# Led_block.net
KiCad netlist of a schematic drawn in Altium Designer
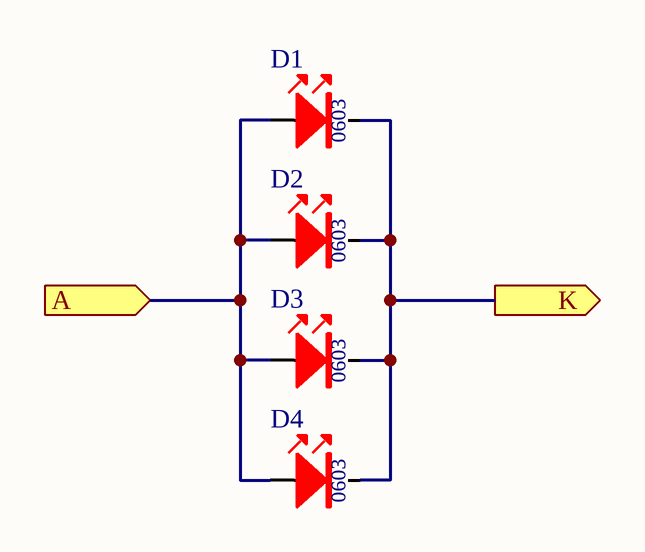
[diagram p0: Led_block.SchDoc]

(export (version "E")
  (design (tool "Eeschema 10.0.6"))
  (components
    (comp (ref "D1")
      (value "Red LED 0603")
      (footprint "OL_0603_1608")
      (description "LED_RED")
      (fields
        (field (name "SCH_FOOTPRINT") "0603")
        (field (name "PART NUMBER") "OL_R_0603_LTST-C193KRKT-5A")
        (field (name "MANUFACTURER") "Lite-On")
      )
      (libsource (lib "Library") (part "OL_R"))
    )
    (comp (ref "D2")
      (value "Red LED 0603")
      (footprint "OL_0603_1608")
      (description "LED_RED")
      (fields
        (field (name "SCH_FOOTPRINT") "0603")
        (field (name "PART NUMBER") "OL_R_0603_LTST-C193KRKT-5A")
        (field (name "MANUFACTURER") "Lite-On")
      )
      (libsource (lib "Library") (part "OL_R"))
    )
    (comp (ref "D3")
      (value "Red LED 0603")
      (footprint "OL_0603_1608")
      (description "LED_RED")
      (fields
        (field (name "SCH_FOOTPRINT") "0603")
        (field (name "PART NUMBER") "OL_R_0603_LTST-C193KRKT-5A")
        (field (name "MANUFACTURER") "Lite-On")
      )
      (libsource (lib "Library") (part "OL_R"))
    )
    (comp (ref "D4")
      (value "Red LED 0603")
      (footprint "OL_0603_1608")
      (description "LED_RED")
      (fields
        (field (name "SCH_FOOTPRINT") "0603")
        (field (name "PART NUMBER") "OL_R_0603_LTST-C193KRKT-5A")
        (field (name "MANUFACTURER") "Lite-On")
      )
      (libsource (lib "Library") (part "OL_R"))
    )
  )
  (nets
    (net (code "1") (name "/A") (class "Default")
      (node (ref "D1") (pin "2") (pinfunction "A_2") (pintype "passive"))
      (node (ref "D2") (pin "2") (pinfunction "A_2") (pintype "passive"))
      (node (ref "D3") (pin "2") (pinfunction "A_2") (pintype "passive"))
      (node (ref "D4") (pin "2") (pinfunction "A_2") (pintype "passive"))
    )
    (net (code "2") (name "/K") (class "Default")
      (node (ref "D1") (pin "1") (pinfunction "K_1") (pintype "passive"))
      (node (ref "D2") (pin "1") (pinfunction "K_1") (pintype "passive"))
      (node (ref "D3") (pin "1") (pinfunction "K_1") (pintype "passive"))
      (node (ref "D4") (pin "1") (pinfunction "K_1") (pintype "passive"))
    )
  )
)
